# 4k-bias-board.net
KiCad netlist of a schematic drawn in Altium Designer
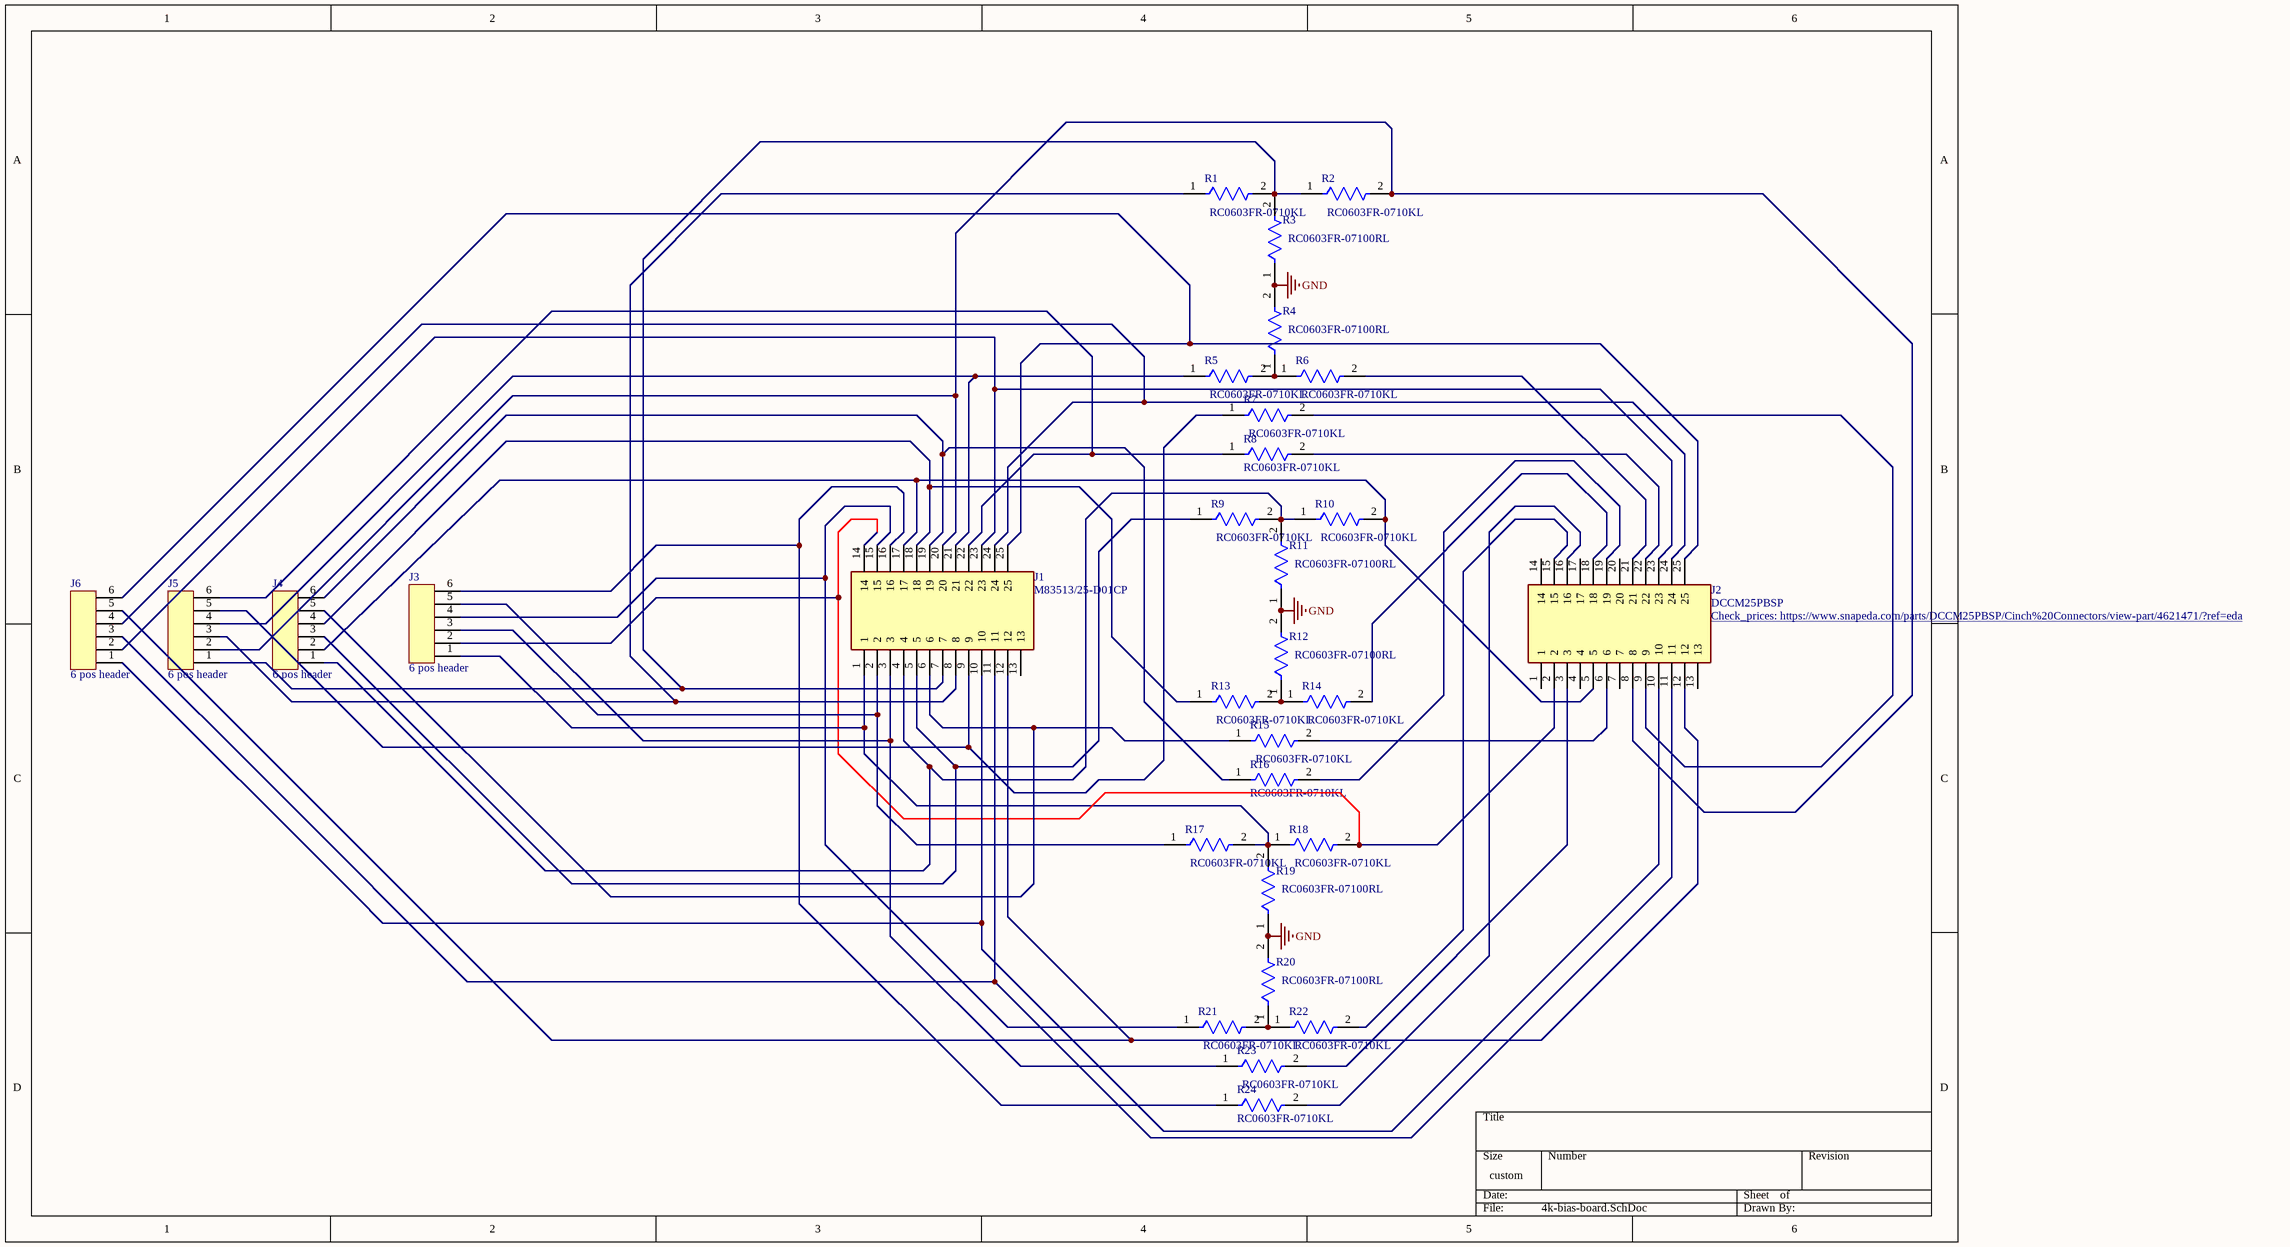
[diagram p0: 4k-bias-board.SchDoc]

(export (version "E")
  (design (tool "Eeschema 10.0.6"))
  (components
    (comp (ref "J1")
      (value "M83513/25-D01CP")
      (footprint "BEL_M83513/25-D01CP")
      (libsource (lib "SchlibLafe") (part "M83513/25-D01CP"))
    )
    (comp (ref "J2")
      (value "DCCM25PBSP")
      (footprint "BEL_DCCM25PBSP")
      (fields
        (field (name "DIGI-KEY_PART_NUMBER") "116-1298-ND")
        (field (name "MF") "Cinch Connectivity Solutions")
        (field (name "CHECK_PRICES") "https://www.snapeda.com/parts/DCCM25PBSP/Cinch%20Connectors/view-part/4621471/?ref=eda")
      )
      (libsource (lib "SchlibLafe") (part "DCCM25PBSP"))
    )
    (comp (ref "J3")
      (value "6 pos header")
      (footprint "6 pin header")
      (description "CONN HEADER VERT 6POS 2.54MM - MTA100 Series")
      (fields
        (field (name "MANUFACTURER_PART_NUMBER") "1755532")
        (field (name "COPYRIGHT") "Copyright (C) 2018 Accelerated Designs. All rights reserved")
      )
      (libsource (lib "SchlibLafe") (part "6 pos header"))
    )
    (comp (ref "J4")
      (value "6 pos header")
      (footprint "6 pin header")
      (description "CONN HEADER VERT 6POS 2.54MM - MTA100 Series")
      (fields
        (field (name "MANUFACTURER_PART_NUMBER") "1755532")
        (field (name "COPYRIGHT") "Copyright (C) 2018 Accelerated Designs. All rights reserved")
      )
      (libsource (lib "SchlibLafe") (part "6 pos header"))
    )
    (comp (ref "J5")
      (value "6 pos header")
      (footprint "6 pin header")
      (description "CONN HEADER VERT 6POS 2.54MM - MTA100 Series")
      (fields
        (field (name "MANUFACTURER_PART_NUMBER") "1755532")
        (field (name "COPYRIGHT") "Copyright (C) 2018 Accelerated Designs. All rights reserved")
      )
      (libsource (lib "SchlibLafe") (part "6 pos header"))
    )
    (comp (ref "J6")
      (value "6 pos header")
      (footprint "6 pin header")
      (description "CONN HEADER VERT 6POS 2.54MM - MTA100 Series")
      (fields
        (field (name "MANUFACTURER_PART_NUMBER") "1755532")
        (field (name "COPYRIGHT") "Copyright (C) 2018 Accelerated Designs. All rights reserved")
      )
      (libsource (lib "SchlibLafe") (part "6 pos header"))
    )
    (comp (ref "R1")
      (value "RC0603FR-0710KL")
      (footprint "FP-RC0603-0_55-IPC_C")
      (description "RES 10K OHM 1% 1/10W 0603")
      (fields (field (name "TOLERANCE") "1%"))
      (libsource (lib "Altium Content Vault") (part "1029c3af85768c4190bb7ad29bc67b5"))
    )
    (comp (ref "R2")
      (value "RC0603FR-0710KL")
      (footprint "FP-RC0603-0_55-IPC_C")
      (description "RES 10K OHM 1% 1/10W 0603")
      (fields (field (name "TOLERANCE") "1%"))
      (libsource (lib "Altium Content Vault") (part "1029c3af85768c4190bb7ad29bc67b5"))
    )
    (comp (ref "R3")
      (value "RC0603FR-07100RL")
      (footprint "FP-RC0603-0_55-MFG")
      (fields (field (name "TOLERANCE") "1%"))
      (libsource (lib "Altium Content Vault") (part "1029c3af85768c4190bb7ad29bc67b5"))
    )
    (comp (ref "R4")
      (value "RC0603FR-07100RL")
      (footprint "FP-RC0603-0_55-MFG")
      (fields (field (name "TOLERANCE") "1%"))
      (libsource (lib "Altium Content Vault") (part "1029c3af85768c4190bb7ad29bc67b5"))
    )
    (comp (ref "R5")
      (value "RC0603FR-0710KL")
      (footprint "FP-RC0603-0_55-IPC_C")
      (description "RES 10K OHM 1% 1/10W 0603")
      (fields (field (name "TOLERANCE") "1%"))
      (libsource (lib "Altium Content Vault") (part "1029c3af85768c4190bb7ad29bc67b5"))
    )
    (comp (ref "R6")
      (value "RC0603FR-0710KL")
      (footprint "FP-RC0603-0_55-IPC_C")
      (description "RES 10K OHM 1% 1/10W 0603")
      (fields (field (name "TOLERANCE") "1%"))
      (libsource (lib "Altium Content Vault") (part "1029c3af85768c4190bb7ad29bc67b5"))
    )
    (comp (ref "R7")
      (value "RC0603FR-0710KL")
      (footprint "FP-RC0603-0_55-IPC_C")
      (description "RES 10K OHM 1% 1/10W 0603")
      (fields (field (name "TOLERANCE") "1%"))
      (libsource (lib "Altium Content Vault") (part "1029c3af85768c4190bb7ad29bc67b5"))
    )
    (comp (ref "R8")
      (value "RC0603FR-0710KL")
      (footprint "FP-RC0603-0_55-IPC_C")
      (description "RES 10K OHM 1% 1/10W 0603")
      (fields (field (name "TOLERANCE") "1%"))
      (libsource (lib "Altium Content Vault") (part "1029c3af85768c4190bb7ad29bc67b5"))
    )
    (comp (ref "R9")
      (value "RC0603FR-0710KL")
      (footprint "FP-RC0603-0_55-IPC_C")
      (description "RES 10K OHM 1% 1/10W 0603")
      (fields (field (name "TOLERANCE") "1%"))
      (libsource (lib "Altium Content Vault") (part "1029c3af85768c4190bb7ad29bc67b5"))
    )
    (comp (ref "R10")
      (value "RC0603FR-0710KL")
      (footprint "FP-RC0603-0_55-IPC_C")
      (description "RES 10K OHM 1% 1/10W 0603")
      (fields (field (name "TOLERANCE") "1%"))
      (libsource (lib "Altium Content Vault") (part "1029c3af85768c4190bb7ad29bc67b5"))
    )
    (comp (ref "R11")
      (value "RC0603FR-07100RL")
      (footprint "FP-RC0603-0_55-MFG")
      (fields (field (name "TOLERANCE") "1%"))
      (libsource (lib "Altium Content Vault") (part "1029c3af85768c4190bb7ad29bc67b5"))
    )
    (comp (ref "R12")
      (value "RC0603FR-07100RL")
      (footprint "FP-RC0603-0_55-MFG")
      (fields (field (name "TOLERANCE") "1%"))
      (libsource (lib "Altium Content Vault") (part "1029c3af85768c4190bb7ad29bc67b5"))
    )
    (comp (ref "R13")
      (value "RC0603FR-0710KL")
      (footprint "FP-RC0603-0_55-IPC_C")
      (description "RES 10K OHM 1% 1/10W 0603")
      (fields (field (name "TOLERANCE") "1%"))
      (libsource (lib "Altium Content Vault") (part "1029c3af85768c4190bb7ad29bc67b5"))
    )
    (comp (ref "R14")
      (value "RC0603FR-0710KL")
      (footprint "FP-RC0603-0_55-IPC_C")
      (description "RES 10K OHM 1% 1/10W 0603")
      (fields (field (name "TOLERANCE") "1%"))
      (libsource (lib "Altium Content Vault") (part "1029c3af85768c4190bb7ad29bc67b5"))
    )
    (comp (ref "R15")
      (value "RC0603FR-0710KL")
      (footprint "FP-RC0603-0_55-IPC_C")
      (description "RES 10K OHM 1% 1/10W 0603")
      (fields (field (name "TOLERANCE") "1%"))
      (libsource (lib "Altium Content Vault") (part "1029c3af85768c4190bb7ad29bc67b5"))
    )
    (comp (ref "R16")
      (value "RC0603FR-0710KL")
      (footprint "FP-RC0603-0_55-IPC_C")
      (description "RES 10K OHM 1% 1/10W 0603")
      (fields (field (name "TOLERANCE") "1%"))
      (libsource (lib "Altium Content Vault") (part "1029c3af85768c4190bb7ad29bc67b5"))
    )
    (comp (ref "R17")
      (value "RC0603FR-0710KL")
      (footprint "FP-RC0603-0_55-IPC_C")
      (description "RES 10K OHM 1% 1/10W 0603")
      (fields (field (name "TOLERANCE") "1%"))
      (libsource (lib "Altium Content Vault") (part "1029c3af85768c4190bb7ad29bc67b5"))
    )
    (comp (ref "R18")
      (value "RC0603FR-0710KL")
      (footprint "FP-RC0603-0_55-IPC_C")
      (description "RES 10K OHM 1% 1/10W 0603")
      (fields (field (name "TOLERANCE") "1%"))
      (libsource (lib "Altium Content Vault") (part "1029c3af85768c4190bb7ad29bc67b5"))
    )
    (comp (ref "R19")
      (value "RC0603FR-07100RL")
      (footprint "FP-RC0603-0_55-MFG")
      (fields (field (name "TOLERANCE") "1%"))
      (libsource (lib "Altium Content Vault") (part "1029c3af85768c4190bb7ad29bc67b5"))
    )
    (comp (ref "R20")
      (value "RC0603FR-07100RL")
      (footprint "FP-RC0603-0_55-MFG")
      (fields (field (name "TOLERANCE") "1%"))
      (libsource (lib "Altium Content Vault") (part "1029c3af85768c4190bb7ad29bc67b5"))
    )
    (comp (ref "R21")
      (value "RC0603FR-0710KL")
      (footprint "FP-RC0603-0_55-IPC_C")
      (description "RES 10K OHM 1% 1/10W 0603")
      (fields (field (name "TOLERANCE") "1%"))
      (libsource (lib "Altium Content Vault") (part "1029c3af85768c4190bb7ad29bc67b5"))
    )
    (comp (ref "R22")
      (value "RC0603FR-0710KL")
      (footprint "FP-RC0603-0_55-IPC_C")
      (description "RES 10K OHM 1% 1/10W 0603")
      (fields (field (name "TOLERANCE") "1%"))
      (libsource (lib "Altium Content Vault") (part "1029c3af85768c4190bb7ad29bc67b5"))
    )
    (comp (ref "R23")
      (value "RC0603FR-0710KL")
      (footprint "FP-RC0603-0_55-IPC_C")
      (description "RES 10K OHM 1% 1/10W 0603")
      (fields (field (name "TOLERANCE") "1%"))
      (libsource (lib "Altium Content Vault") (part "1029c3af85768c4190bb7ad29bc67b5"))
    )
    (comp (ref "R24")
      (value "RC0603FR-0710KL")
      (footprint "FP-RC0603-0_55-IPC_C")
      (description "RES 10K OHM 1% 1/10W 0603")
      (fields (field (name "TOLERANCE") "1%"))
      (libsource (lib "Altium Content Vault") (part "1029c3af85768c4190bb7ad29bc67b5"))
    )
  )
  (nets
    (net (code "1") (name "GND") (class "Default")
      (node (ref "R11") (pin "1") (pinfunction "1_1") (pintype "passive"))
      (node (ref "R12") (pin "2") (pinfunction "2_2") (pintype "passive"))
      (node (ref "R19") (pin "1") (pinfunction "1_1") (pintype "passive"))
      (node (ref "R20") (pin "2") (pinfunction "2_2") (pintype "passive"))
      (node (ref "R3") (pin "1") (pinfunction "1_1") (pintype "passive"))
      (node (ref "R4") (pin "2") (pinfunction "2_2") (pintype "passive"))
    )
    (net (code "2") (name "Net-(J1-Pad1)") (class "Default")
      (node (ref "J1") (pin "1") (pinfunction "1_1") (pintype "passive"))
      (node (ref "J3") (pin "1") (pinfunction "1_1") (pintype "passive"))
      (node (ref "R17") (pin "2") (pinfunction "2_2") (pintype "passive"))
      (node (ref "R18") (pin "1") (pinfunction "1_1") (pintype "passive"))
      (node (ref "R19") (pin "2") (pinfunction "2_2") (pintype "passive"))
    )
    (net (code "3") (name "Net-(J1-Pad2)") (class "Default")
      (node (ref "J1") (pin "2") (pinfunction "2_2") (pintype "passive"))
      (node (ref "J3") (pin "3") (pinfunction "3_3") (pintype "passive"))
      (node (ref "R17") (pin "1") (pinfunction "1_1") (pintype "passive"))
    )
    (net (code "4") (name "Net-(J1-Pad3)") (class "Default")
      (node (ref "J1") (pin "3") (pinfunction "3_3") (pintype "passive"))
      (node (ref "J3") (pin "5") (pinfunction "5_5") (pintype "passive"))
      (node (ref "R23") (pin "1") (pinfunction "1_1") (pintype "passive"))
    )
    (net (code "5") (name "Net-(J1-Pad4)") (class "Default")
      (node (ref "J1") (pin "4") (pinfunction "4_4") (pintype "passive"))
      (node (ref "J4") (pin "1") (pinfunction "1_1") (pintype "passive"))
      (node (ref "R10") (pin "1") (pinfunction "1_1") (pintype "passive"))
      (node (ref "R11") (pin "2") (pinfunction "2_2") (pintype "passive"))
      (node (ref "R9") (pin "2") (pinfunction "2_2") (pintype "passive"))
    )
    (net (code "6") (name "Net-(J1-Pad5)") (class "Default")
      (node (ref "J1") (pin "5") (pinfunction "5_5") (pintype "passive"))
      (node (ref "J4") (pin "3") (pinfunction "3_3") (pintype "passive"))
      (node (ref "R9") (pin "1") (pinfunction "1_1") (pintype "passive"))
    )
    (net (code "7") (name "Net-(J1-Pad6)") (class "Default")
      (node (ref "J1") (pin "6") (pinfunction "6_6") (pintype "passive"))
      (node (ref "J4") (pin "5") (pinfunction "5_5") (pintype "passive"))
      (node (ref "R15") (pin "1") (pinfunction "1_1") (pintype "passive"))
    )
    (net (code "8") (name "Net-(J1-Pad7)") (class "Default")
      (node (ref "J1") (pin "7") (pinfunction "7_7") (pintype "passive"))
      (node (ref "J5") (pin "1") (pinfunction "1_1") (pintype "passive"))
      (node (ref "R1") (pin "2") (pinfunction "2_2") (pintype "passive"))
      (node (ref "R2") (pin "1") (pinfunction "1_1") (pintype "passive"))
      (node (ref "R3") (pin "2") (pinfunction "2_2") (pintype "passive"))
    )
    (net (code "9") (name "Net-(J1-Pad8)") (class "Default")
      (node (ref "J1") (pin "8") (pinfunction "8_8") (pintype "passive"))
      (node (ref "J5") (pin "3") (pinfunction "3_3") (pintype "passive"))
      (node (ref "R1") (pin "1") (pinfunction "1_1") (pintype "passive"))
    )
    (net (code "10") (name "Net-(J1-Pad9)") (class "Default")
      (node (ref "J1") (pin "9") (pinfunction "9_9") (pintype "passive"))
      (node (ref "J5") (pin "5") (pinfunction "5_5") (pintype "passive"))
      (node (ref "R7") (pin "1") (pinfunction "1_1") (pintype "passive"))
    )
    (net (code "11") (name "Net-(J1-Pad10)") (class "Default")
      (node (ref "J1") (pin "10") (pinfunction "10_10") (pintype "passive"))
      (node (ref "J2") (pin "10") (pinfunction "10_10") (pintype "passive"))
      (node (ref "J6") (pin "1") (pinfunction "1_1") (pintype "passive"))
    )
    (net (code "12") (name "Net-(J1-Pad11)") (class "Default")
      (node (ref "J1") (pin "11") (pinfunction "11_11") (pintype "passive"))
      (node (ref "J2") (pin "11") (pinfunction "11_11") (pintype "passive"))
      (node (ref "J6") (pin "3") (pinfunction "3_3") (pintype "passive"))
    )
    (net (code "13") (name "Net-(J1-Pad12)") (class "Default")
      (node (ref "J1") (pin "12") (pinfunction "12_12") (pintype "passive"))
      (node (ref "J2") (pin "12") (pinfunction "12_12") (pintype "passive"))
      (node (ref "J6") (pin "5") (pinfunction "5_5") (pintype "passive"))
    )
    (net (code "14") (name "Net-(J1-Pad14)") (class "Default")
      (node (ref "J1") (pin "14") (pinfunction "14_14") (pintype "passive"))
      (node (ref "J2") (pin "2") (pinfunction "2_2") (pintype "passive"))
      (node (ref "J3") (pin "2") (pinfunction "2_2") (pintype "passive"))
      (node (ref "R18") (pin "2") (pinfunction "2_2") (pintype "passive"))
    )
    (net (code "15") (name "Net-(J1-Pad15)") (class "Default")
      (node (ref "J1") (pin "15") (pinfunction "15_15") (pintype "passive"))
      (node (ref "J3") (pin "4") (pinfunction "4_4") (pintype "passive"))
      (node (ref "R21") (pin "1") (pinfunction "1_1") (pintype "passive"))
    )
    (net (code "16") (name "Net-(J1-Pad16)") (class "Default")
      (node (ref "J1") (pin "16") (pinfunction "16_16") (pintype "passive"))
      (node (ref "J3") (pin "6") (pinfunction "6_6") (pintype "passive"))
      (node (ref "R24") (pin "1") (pinfunction "1_1") (pintype "passive"))
    )
    (net (code "17") (name "Net-(J1-Pad17)") (class "Default")
      (node (ref "J1") (pin "17") (pinfunction "17_17") (pintype "passive"))
      (node (ref "J2") (pin "5") (pinfunction "5_5") (pintype "passive"))
      (node (ref "J4") (pin "2") (pinfunction "2_2") (pintype "passive"))
      (node (ref "R10") (pin "2") (pinfunction "2_2") (pintype "passive"))
    )
    (net (code "18") (name "Net-(J1-Pad18)") (class "Default")
      (node (ref "J1") (pin "18") (pinfunction "18_18") (pintype "passive"))
      (node (ref "J4") (pin "4") (pinfunction "4_4") (pintype "passive"))
      (node (ref "R13") (pin "1") (pinfunction "1_1") (pintype "passive"))
    )
    (net (code "19") (name "Net-(J1-Pad19)") (class "Default")
      (node (ref "J1") (pin "19") (pinfunction "19_19") (pintype "passive"))
      (node (ref "J4") (pin "6") (pinfunction "6_6") (pintype "passive"))
      (node (ref "R16") (pin "1") (pinfunction "1_1") (pintype "passive"))
    )
    (net (code "20") (name "Net-(J1-Pad20)") (class "Default")
      (node (ref "J1") (pin "20") (pinfunction "20_20") (pintype "passive"))
      (node (ref "J2") (pin "8") (pinfunction "8_8") (pintype "passive"))
      (node (ref "J5") (pin "2") (pinfunction "2_2") (pintype "passive"))
      (node (ref "R2") (pin "2") (pinfunction "2_2") (pintype "passive"))
    )
    (net (code "21") (name "Net-(J1-Pad21)") (class "Default")
      (node (ref "J1") (pin "21") (pinfunction "21_21") (pintype "passive"))
      (node (ref "J5") (pin "4") (pinfunction "4_4") (pintype "passive"))
      (node (ref "R5") (pin "1") (pinfunction "1_1") (pintype "passive"))
    )
    (net (code "22") (name "Net-(J1-Pad22)") (class "Default")
      (node (ref "J1") (pin "22") (pinfunction "22_22") (pintype "passive"))
      (node (ref "J5") (pin "6") (pinfunction "6_6") (pintype "passive"))
      (node (ref "R8") (pin "1") (pinfunction "1_1") (pintype "passive"))
    )
    (net (code "23") (name "Net-(J1-Pad23)") (class "Default")
      (node (ref "J1") (pin "23") (pinfunction "23_23") (pintype "passive"))
      (node (ref "J2") (pin "23") (pinfunction "23_23") (pintype "passive"))
      (node (ref "J6") (pin "2") (pinfunction "2_2") (pintype "passive"))
    )
    (net (code "24") (name "Net-(J1-Pad24)") (class "Default")
      (node (ref "J1") (pin "24") (pinfunction "24_24") (pintype "passive"))
      (node (ref "J2") (pin "24") (pinfunction "24_24") (pintype "passive"))
      (node (ref "J6") (pin "4") (pinfunction "4_4") (pintype "passive"))
    )
    (net (code "25") (name "Net-(J1-Pad25)") (class "Default")
      (node (ref "J1") (pin "25") (pinfunction "25_25") (pintype "passive"))
      (node (ref "J2") (pin "25") (pinfunction "25_25") (pintype "passive"))
      (node (ref "J6") (pin "6") (pinfunction "6_6") (pintype "passive"))
    )
    (net (code "26") (name "Net-(J2-Pad3)") (class "Default")
      (node (ref "J2") (pin "3") (pinfunction "3_3") (pintype "passive"))
      (node (ref "R23") (pin "2") (pinfunction "2_2") (pintype "passive"))
    )
    (net (code "27") (name "Net-(J2-Pad6)") (class "Default")
      (node (ref "J2") (pin "6") (pinfunction "6_6") (pintype "passive"))
      (node (ref "R15") (pin "2") (pinfunction "2_2") (pintype "passive"))
    )
    (net (code "28") (name "Net-(J2-Pad9)") (class "Default")
      (node (ref "J2") (pin "9") (pinfunction "9_9") (pintype "passive"))
      (node (ref "R7") (pin "2") (pinfunction "2_2") (pintype "passive"))
    )
    (net (code "29") (name "Net-(J2-Pad15)") (class "Default")
      (node (ref "J2") (pin "15") (pinfunction "15_15") (pintype "passive"))
      (node (ref "R22") (pin "2") (pinfunction "2_2") (pintype "passive"))
    )
    (net (code "30") (name "Net-(J2-Pad16)") (class "Default")
      (node (ref "J2") (pin "16") (pinfunction "16_16") (pintype "passive"))
      (node (ref "R24") (pin "2") (pinfunction "2_2") (pintype "passive"))
    )
    (net (code "31") (name "Net-(J2-Pad18)") (class "Default")
      (node (ref "J2") (pin "18") (pinfunction "18_18") (pintype "passive"))
      (node (ref "R14") (pin "2") (pinfunction "2_2") (pintype "passive"))
    )
    (net (code "32") (name "Net-(J2-Pad19)") (class "Default")
      (node (ref "J2") (pin "19") (pinfunction "19_19") (pintype "passive"))
      (node (ref "R16") (pin "2") (pinfunction "2_2") (pintype "passive"))
    )
    (net (code "33") (name "Net-(J2-Pad21)") (class "Default")
      (node (ref "J2") (pin "21") (pinfunction "21_21") (pintype "passive"))
      (node (ref "R6") (pin "2") (pinfunction "2_2") (pintype "passive"))
    )
    (net (code "34") (name "Net-(J2-Pad22)") (class "Default")
      (node (ref "J2") (pin "22") (pinfunction "22_22") (pintype "passive"))
      (node (ref "R8") (pin "2") (pinfunction "2_2") (pintype "passive"))
    )
    (net (code "35") (name "Net-(R4-Pad1)") (class "Default")
      (node (ref "R4") (pin "1") (pinfunction "1_1") (pintype "passive"))
      (node (ref "R5") (pin "2") (pinfunction "2_2") (pintype "passive"))
      (node (ref "R6") (pin "1") (pinfunction "1_1") (pintype "passive"))
    )
    (net (code "36") (name "Net-(R12-Pad1)") (class "Default")
      (node (ref "R12") (pin "1") (pinfunction "1_1") (pintype "passive"))
      (node (ref "R13") (pin "2") (pinfunction "2_2") (pintype "passive"))
      (node (ref "R14") (pin "1") (pinfunction "1_1") (pintype "passive"))
    )
    (net (code "37") (name "Net-(R20-Pad1)") (class "Default")
      (node (ref "R20") (pin "1") (pinfunction "1_1") (pintype "passive"))
      (node (ref "R21") (pin "2") (pinfunction "2_2") (pintype "passive"))
      (node (ref "R22") (pin "1") (pinfunction "1_1") (pintype "passive"))
    )
    (net (code "38") (name "unconnected-(J1-Pad13)") (class "Default")
      (node (ref "J1") (pin "13") (pinfunction "13_13") (pintype "passive"))
    )
    (net (code "39") (name "unconnected-(J2-Pad1)") (class "Default")
      (node (ref "J2") (pin "1") (pinfunction "1_1") (pintype "passive"))
    )
    (net (code "40") (name "unconnected-(J2-Pad4)") (class "Default")
      (node (ref "J2") (pin "4") (pinfunction "4_4") (pintype "passive"))
    )
    (net (code "41") (name "unconnected-(J2-Pad7)") (class "Default")
      (node (ref "J2") (pin "7") (pinfunction "7_7") (pintype "passive"))
    )
    (net (code "42") (name "unconnected-(J2-Pad13)") (class "Default")
      (node (ref "J2") (pin "13") (pinfunction "13_13") (pintype "passive"))
    )
    (net (code "43") (name "unconnected-(J2-Pad14)") (class "Default")
      (node (ref "J2") (pin "14") (pinfunction "14_14") (pintype "passive"))
    )
    (net (code "44") (name "unconnected-(J2-Pad17)") (class "Default")
      (node (ref "J2") (pin "17") (pinfunction "17_17") (pintype "passive"))
    )
    (net (code "45") (name "unconnected-(J2-Pad20)") (class "Default")
      (node (ref "J2") (pin "20") (pinfunction "20_20") (pintype "passive"))
    )
  )
)
